# ScreenCircuitV0_2.net
KiCad netlist of a schematic drawn in EAGLE
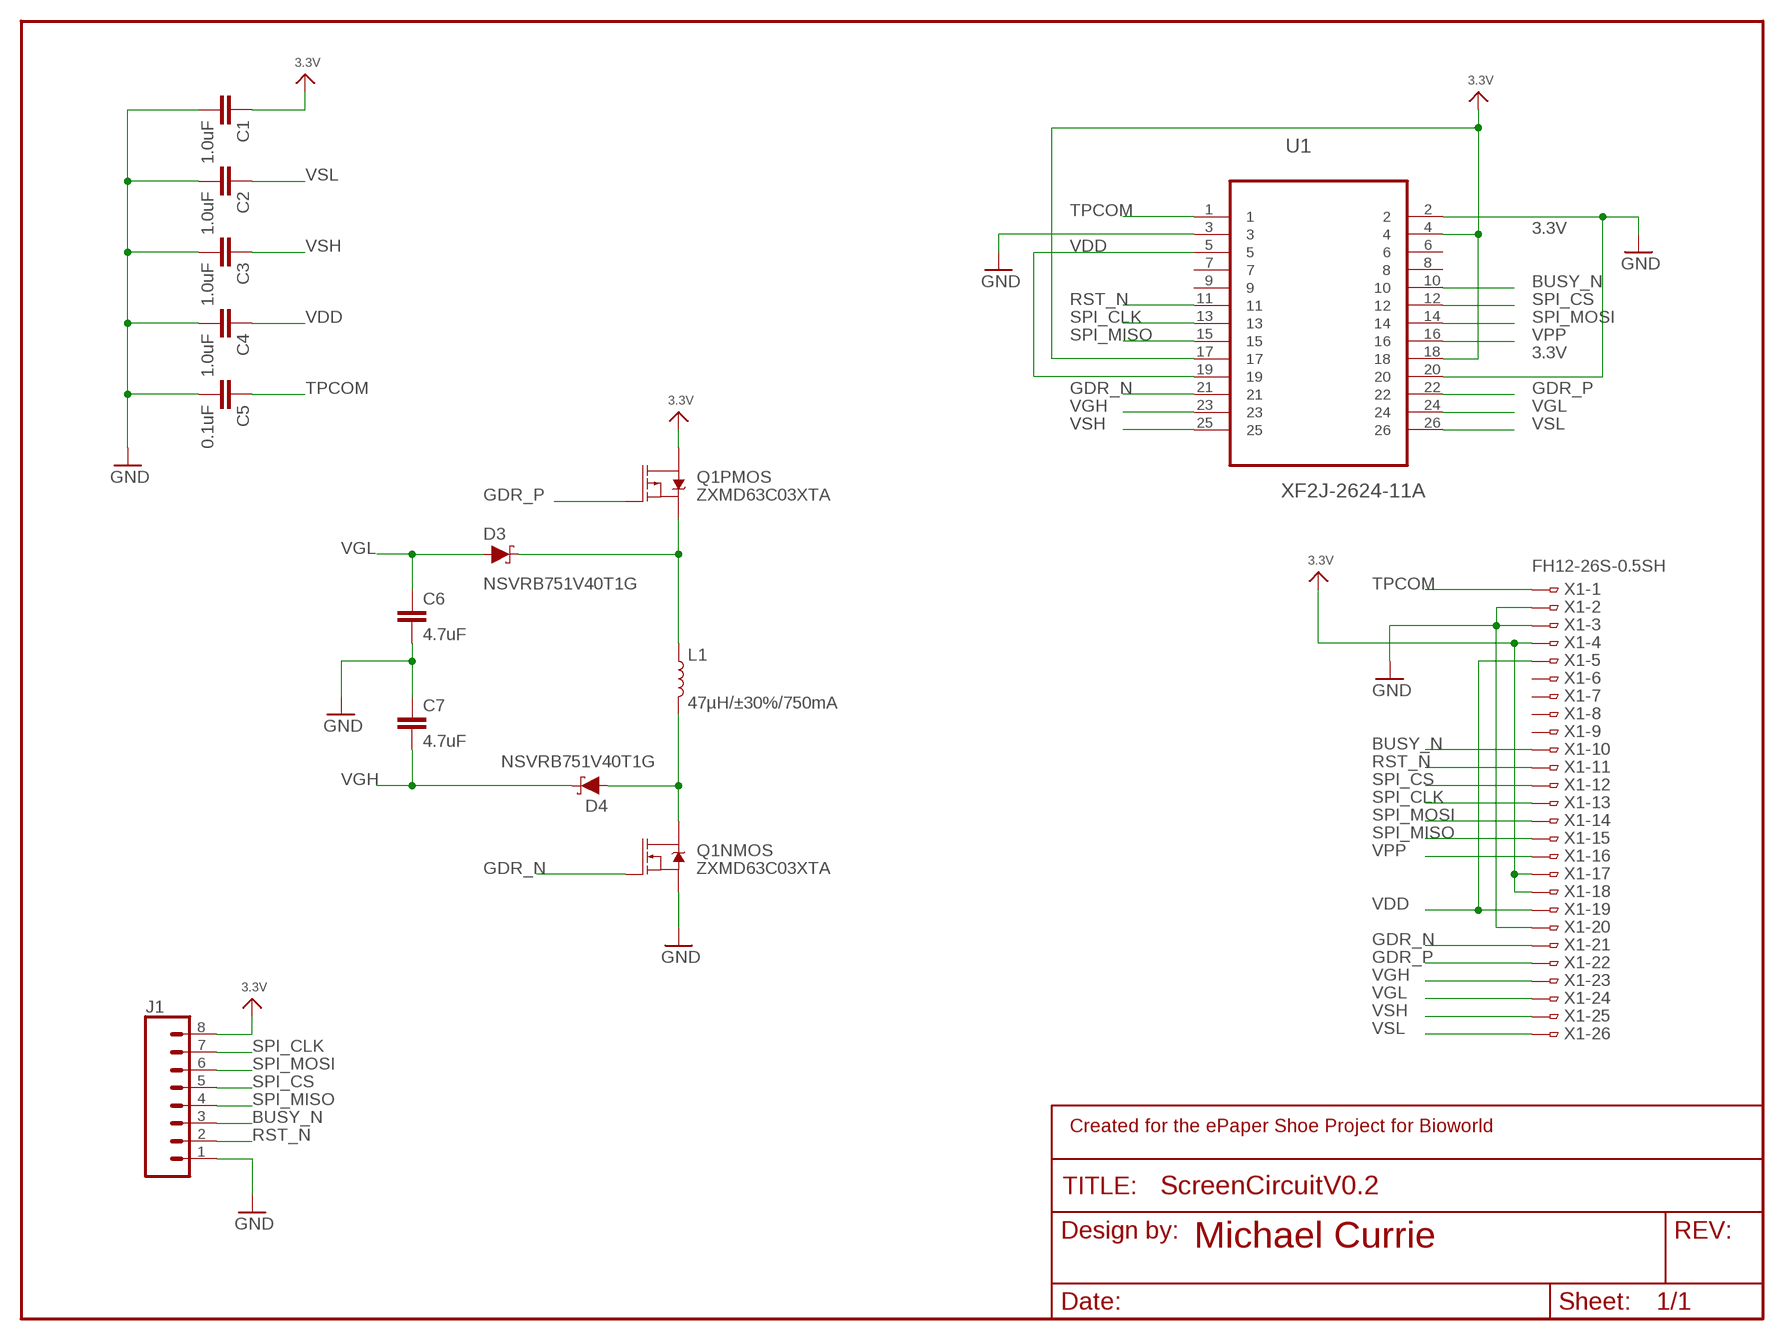
[diagram p0: schematic, sheet 1]

(export (version "E")
  (design (tool "Eeschema 10.0.6"))
  (components
    (comp (ref "C1")
      (value "1.0uF")
      (footprint "eagle-import:1206")
      (libsource (lib "eagle-import") (part "1.0UF-1206-50V-10%"))
    )
    (comp (ref "C2")
      (value "1.0uF")
      (footprint "eagle-import:1206")
      (libsource (lib "eagle-import") (part "1.0UF-1206-50V-10%"))
    )
    (comp (ref "C3")
      (value "1.0uF")
      (footprint "eagle-import:1206")
      (libsource (lib "eagle-import") (part "1.0UF-1206-50V-10%"))
    )
    (comp (ref "C4")
      (value "1.0uF")
      (footprint "eagle-import:1206")
      (libsource (lib "eagle-import") (part "1.0UF-1206-50V-10%"))
    )
    (comp (ref "C5")
      (value "0.1uF")
      (footprint "eagle-import:0603")
      (libsource (lib "eagle-import") (part "0.1UF-0603-100V-10%"))
    )
    (comp (ref "C6")
      (value "4.7uF")
      (footprint "eagle-import:1206")
      (libsource (lib "eagle-import") (part "4.7UF-1206-16V-(+80/-20%)"))
    )
    (comp (ref "C7")
      (value "4.7uF")
      (footprint "eagle-import:1206")
      (libsource (lib "eagle-import") (part "4.7UF-1206-16V-(+80/-20%)"))
    )
    (comp (ref "D3")
      (value "0.5A/40V/420mV")
      (footprint "eagle-import:SOD-323")
      (libsource (lib "eagle-import") (part "DIODE-SCHOTTKY-PMEG4005EJ"))
    )
    (comp (ref "D4")
      (value "0.5A/40V/420mV")
      (footprint "eagle-import:SOD-323")
      (libsource (lib "eagle-import") (part "DIODE-SCHOTTKY-PMEG4005EJ"))
    )
    (comp (ref "FRAME1")
      (value "FRAME-LETTER-MICHAELNO_PACKAGE")
      (footprint "eagle-import:DUMMY")
      (fields (field (name "DESIGNER") "Nobody"))
      (libsource (lib "eagle-import") (part "FRAME-LETTER-MICHAELNO_PACKAGE"))
    )
    (comp (ref "J1")
      (value "CONN_08\"")
      (footprint "eagle-import:1X08")
      (libsource (lib "eagle-import") (part "CONN_08{dblquote}"))
    )
    (comp (ref "L1")
      (value "47µH/±30%/750mA")
      (footprint "eagle-import:CR54")
      (libsource (lib "eagle-import") (part "INDUCTOR-CR54-47UH"))
    )
    (comp (ref "Q1")
      (value "IRF7509")
      (footprint "eagle-import:MSOP8")
      (libsource (lib "eagle-import") (part "IRF7509"))
    )
    (comp (ref "U1")
      (value "XF2J-2624-11A")
      (footprint "eagle-import:OMRON_XF2J-2624-11A")
      (libsource (lib "eagle-import") (part "XF2J-2624-11A"))
    )
    (comp (ref "X1")
      (value "FH12-26S-0.5SH")
      (footprint "eagle-import:FH12-26S-0.5SH")
      (fields (field (name "MPN") "FH12-26S-0.5SH(55)"))
      (libsource (lib "eagle-import") (part "FH12-26S-0.5SH"))
    )
  )
  (nets
    (net (code "1") (name "/BUSY_N") (class "Default")
      (node (ref "J1") (pin "3") (pinfunction "3_3") (pintype "passive"))
      (node (ref "U1") (pin "10") (pinfunction "10_10") (pintype "passive"))
      (node (ref "X1") (pin "10") (pinfunction "1_10") (pintype "passive"))
    )
    (net (code "2") (name "/GDR_N") (class "Default")
      (node (ref "Q1") (pin "2") (pinfunction "G_2") (pintype "bidirectional"))
      (node (ref "U1") (pin "21") (pinfunction "21_21") (pintype "passive"))
      (node (ref "X1") (pin "21") (pinfunction "1_21") (pintype "passive"))
    )
    (net (code "3") (name "/GDR_P") (class "Default")
      (node (ref "Q1") (pin "4") (pinfunction "G_4") (pintype "bidirectional"))
      (node (ref "U1") (pin "22") (pinfunction "22_22") (pintype "passive"))
      (node (ref "X1") (pin "22") (pinfunction "1_22") (pintype "passive"))
    )
    (net (code "4") (name "/RST_N") (class "Default")
      (node (ref "J1") (pin "2") (pinfunction "2_2") (pintype "passive"))
      (node (ref "U1") (pin "11") (pinfunction "11_11") (pintype "passive"))
      (node (ref "X1") (pin "11") (pinfunction "1_11") (pintype "passive"))
    )
    (net (code "5") (name "/SPI_CLK") (class "Default")
      (node (ref "J1") (pin "7") (pinfunction "7_7") (pintype "passive"))
      (node (ref "U1") (pin "13") (pinfunction "13_13") (pintype "passive"))
      (node (ref "X1") (pin "13") (pinfunction "1_13") (pintype "passive"))
    )
    (net (code "6") (name "/SPI_CS") (class "Default")
      (node (ref "J1") (pin "5") (pinfunction "5_5") (pintype "passive"))
      (node (ref "U1") (pin "12") (pinfunction "12_12") (pintype "passive"))
      (node (ref "X1") (pin "12") (pinfunction "1_12") (pintype "passive"))
    )
    (net (code "7") (name "/SPI_MISO") (class "Default")
      (node (ref "J1") (pin "4") (pinfunction "4_4") (pintype "passive"))
      (node (ref "U1") (pin "15") (pinfunction "15_15") (pintype "passive"))
      (node (ref "X1") (pin "15") (pinfunction "1_15") (pintype "passive"))
    )
    (net (code "8") (name "/SPI_MOSI") (class "Default")
      (node (ref "J1") (pin "6") (pinfunction "6_6") (pintype "passive"))
      (node (ref "U1") (pin "14") (pinfunction "14_14") (pintype "passive"))
      (node (ref "X1") (pin "14") (pinfunction "1_14") (pintype "passive"))
    )
    (net (code "9") (name "/TPCOM") (class "Default")
      (node (ref "C5") (pin "1") (pinfunction "1_1") (pintype "passive"))
      (node (ref "U1") (pin "1") (pinfunction "1_1") (pintype "passive"))
      (node (ref "X1") (pin "1") (pinfunction "1_1") (pintype "passive"))
    )
    (net (code "10") (name "/VDD") (class "Default")
      (node (ref "C4") (pin "1") (pinfunction "1_1") (pintype "passive"))
      (node (ref "U1") (pin "19") (pinfunction "19_19") (pintype "passive"))
      (node (ref "U1") (pin "5") (pinfunction "5_5") (pintype "passive"))
      (node (ref "X1") (pin "19") (pinfunction "1_19") (pintype "passive"))
      (node (ref "X1") (pin "5") (pinfunction "1_5") (pintype "passive"))
    )
    (net (code "11") (name "/VGH") (class "Default")
      (node (ref "C7") (pin "2") (pinfunction "2_2") (pintype "passive"))
      (node (ref "D4") (pin "C") (pinfunction "C_C") (pintype "passive"))
      (node (ref "U1") (pin "23") (pinfunction "23_23") (pintype "passive"))
      (node (ref "X1") (pin "23") (pinfunction "1_23") (pintype "passive"))
    )
    (net (code "12") (name "/VGL") (class "Default")
      (node (ref "C6") (pin "1") (pinfunction "1_1") (pintype "passive"))
      (node (ref "D3") (pin "A") (pinfunction "A_A") (pintype "passive"))
      (node (ref "U1") (pin "24") (pinfunction "24_24") (pintype "passive"))
      (node (ref "X1") (pin "24") (pinfunction "1_24") (pintype "passive"))
    )
    (net (code "13") (name "/VPP") (class "Default")
      (node (ref "U1") (pin "16") (pinfunction "16_16") (pintype "passive"))
      (node (ref "X1") (pin "16") (pinfunction "1_16") (pintype "passive"))
    )
    (net (code "14") (name "/VSH") (class "Default")
      (node (ref "C3") (pin "1") (pinfunction "1_1") (pintype "passive"))
      (node (ref "U1") (pin "25") (pinfunction "25_25") (pintype "passive"))
      (node (ref "X1") (pin "25") (pinfunction "1_25") (pintype "passive"))
    )
    (net (code "15") (name "/VSL") (class "Default")
      (node (ref "C2") (pin "1") (pinfunction "1_1") (pintype "passive"))
      (node (ref "U1") (pin "26") (pinfunction "26_26") (pintype "passive"))
      (node (ref "X1") (pin "26") (pinfunction "1_26") (pintype "passive"))
    )
    (net (code "16") (name "3.3V") (class "Default")
      (node (ref "C1") (pin "1") (pinfunction "1_1") (pintype "passive"))
      (node (ref "J1") (pin "8") (pinfunction "8_8") (pintype "passive"))
      (node (ref "Q1") (pin "5") (pinfunction "D_5") (pintype "bidirectional"))
      (node (ref "Q1") (pin "6") (pinfunction "D_6") (pintype "bidirectional"))
      (node (ref "U1") (pin "17") (pinfunction "17_17") (pintype "passive"))
      (node (ref "U1") (pin "18") (pinfunction "18_18") (pintype "passive"))
      (node (ref "U1") (pin "4") (pinfunction "4_4") (pintype "passive"))
      (node (ref "X1") (pin "17") (pinfunction "1_17") (pintype "passive"))
      (node (ref "X1") (pin "18") (pinfunction "1_18") (pintype "passive"))
      (node (ref "X1") (pin "4") (pinfunction "1_4") (pintype "passive"))
    )
    (net (code "17") (name "GND") (class "Default")
      (node (ref "C1") (pin "2") (pinfunction "2_2") (pintype "passive"))
      (node (ref "C2") (pin "2") (pinfunction "2_2") (pintype "passive"))
      (node (ref "C3") (pin "2") (pinfunction "2_2") (pintype "passive"))
      (node (ref "C4") (pin "2") (pinfunction "2_2") (pintype "passive"))
      (node (ref "C5") (pin "2") (pinfunction "2_2") (pintype "passive"))
      (node (ref "C6") (pin "2") (pinfunction "2_2") (pintype "passive"))
      (node (ref "C7") (pin "1") (pinfunction "1_1") (pintype "passive"))
      (node (ref "J1") (pin "1") (pinfunction "1_1") (pintype "passive"))
      (node (ref "Q1") (pin "1") (pinfunction "S_1") (pintype "bidirectional"))
      (node (ref "U1") (pin "2") (pinfunction "2_2") (pintype "passive"))
      (node (ref "U1") (pin "20") (pinfunction "20_20") (pintype "passive"))
      (node (ref "U1") (pin "3") (pinfunction "3_3") (pintype "passive"))
      (node (ref "X1") (pin "2") (pinfunction "1_2") (pintype "passive"))
      (node (ref "X1") (pin "20") (pinfunction "1_20") (pintype "passive"))
      (node (ref "X1") (pin "3") (pinfunction "1_3") (pintype "passive"))
    )
    (net (code "18") (name "Net-(L1-1)") (class "Default")
      (node (ref "D3") (pin "C") (pinfunction "C_C") (pintype "passive"))
      (node (ref "L1") (pin "P$1") (pinfunction "1_P$1") (pintype "passive"))
      (node (ref "Q1") (pin "3") (pinfunction "S_3") (pintype "bidirectional"))
    )
    (net (code "19") (name "Net-(L1-2)") (class "Default")
      (node (ref "D4") (pin "A") (pinfunction "A_A") (pintype "passive"))
      (node (ref "L1") (pin "P$2") (pinfunction "2_P$2") (pintype "passive"))
      (node (ref "Q1") (pin "7") (pinfunction "D_7") (pintype "bidirectional"))
      (node (ref "Q1") (pin "8") (pinfunction "D_8") (pintype "bidirectional"))
    )
    (net (code "20") (name "unconnected-(U1-Pad6)") (class "Default")
      (node (ref "U1") (pin "6") (pinfunction "6_6") (pintype "passive"))
    )
    (net (code "21") (name "unconnected-(U1-Pad7)") (class "Default")
      (node (ref "U1") (pin "7") (pinfunction "7_7") (pintype "passive"))
    )
    (net (code "22") (name "unconnected-(U1-Pad8)") (class "Default")
      (node (ref "U1") (pin "8") (pinfunction "8_8") (pintype "passive"))
    )
    (net (code "23") (name "unconnected-(U1-Pad9)") (class "Default")
      (node (ref "U1") (pin "9") (pinfunction "9_9") (pintype "passive"))
    )
    (net (code "24") (name "unconnected-(X1W-1-Pad6)") (class "Default")
      (node (ref "X1") (pin "6") (pinfunction "1_6") (pintype "passive"))
    )
    (net (code "25") (name "unconnected-(X1X-1-Pad7)") (class "Default")
      (node (ref "X1") (pin "7") (pinfunction "1_7") (pintype "passive"))
    )
    (net (code "26") (name "unconnected-(X1Y-1-Pad8)") (class "Default")
      (node (ref "X1") (pin "8") (pinfunction "1_8") (pintype "passive"))
    )
    (net (code "27") (name "unconnected-(X1Z-1-Pad9)") (class "Default")
      (node (ref "X1") (pin "9") (pinfunction "1_9") (pintype "passive"))
    )
  )
)
